# GPIO.net
KiCad netlist of a schematic drawn in Altium Designer
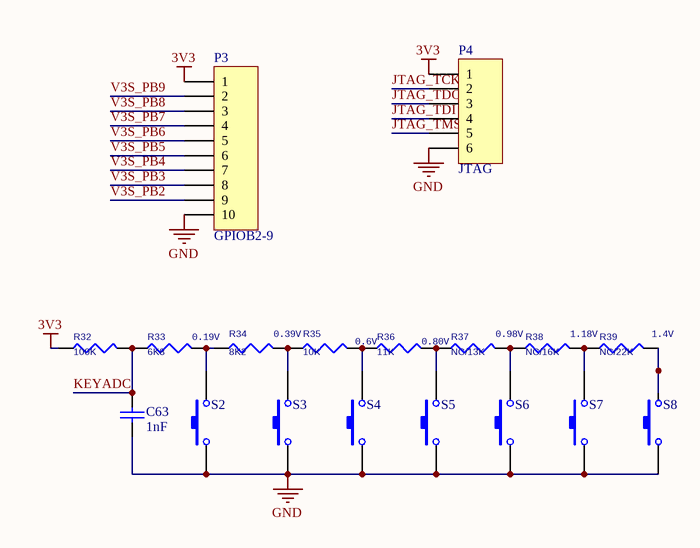
[diagram p0: GPIO.SchDoc]

(export (version "E")
  (design (tool "Eeschema 10.0.6"))
  (components
    (comp (ref "C63")
      (value "1nF")
      (footprint "0603C")
      (description "0603 Ceramic Capacitor")
      (fields (field (name "Comment") "103") (field (name "PUBLISHER") "Altium Limited"))
      (libsource (lib "Miscellaneous Devices") (part "Cap"))
    )
    (comp (ref "P3")
      (value "GPIOB2-9")
      (footprint "HDR1X10")
      (description "Header, 10-Pin")
      (fields (field (name "PUBLISHER") "Altium Limited"))
      (libsource (lib "Miscellaneous Connectors") (part "Header 10"))
    )
    (comp (ref "P4")
      (value "JTAG")
      (footprint "HDR1X6")
      (description "Header, 6-Pin")
      (fields (field (name "PUBLISHER") "Altium Limited"))
      (libsource (lib "Miscellaneous Connectors") (part "Header 6"))
    )
    (comp (ref "R32") (value "100K") (footprint "0603R") (libsource (lib "*") (part "R1 0805_Dup2")))
    (comp (ref "R33") (value "6K8") (footprint "0603R") (libsource (lib "*") (part "R1 0805_Dup2")))
    (comp (ref "R34") (value "8K2") (footprint "0603R") (libsource (lib "*") (part "R1 0805_Dup2")))
    (comp (ref "R35") (value "10K") (footprint "0603R") (libsource (lib "*") (part "R1 0805_Dup2")))
    (comp (ref "R36") (value "11K") (footprint "0603R") (libsource (lib "*") (part "R1 0805_Dup2")))
    (comp (ref "R37") (value "NC/13K") (footprint "0603R") (libsource (lib "*") (part "R1 0805")))
    (comp (ref "R38") (value "NC/16K") (footprint "0603R") (libsource (lib "*") (part "R1 0805")))
    (comp (ref "R39") (value "NC/22K") (footprint "0603R") (libsource (lib "*") (part "R1 0805")))
    (comp (ref "S2")
      (value "SW-PB")
      (footprint "Switch_SMT-022S-H2.5")
      (description "Switch")
      (fields (field (name "PUBLISHER") "Altium Limited"))
      (libsource (lib "Miscellaneous Devices") (part "SW-PB"))
    )
    (comp (ref "S3")
      (value "SW-PB")
      (footprint "Switch_SMT-022S-H2.5")
      (description "Switch")
      (fields (field (name "PUBLISHER") "Altium Limited"))
      (libsource (lib "Miscellaneous Devices") (part "SW-PB"))
    )
    (comp (ref "S4")
      (value "SW-PB")
      (footprint "Switch_SMT-022S-H2.5")
      (description "Switch")
      (fields (field (name "PUBLISHER") "Altium Limited"))
      (libsource (lib "Miscellaneous Devices") (part "SW-PB"))
    )
    (comp (ref "S5")
      (value "SW-PB")
      (footprint "Switch_SMT-022S-H2.5")
      (description "Switch")
      (fields (field (name "PUBLISHER") "Altium Limited"))
      (libsource (lib "Miscellaneous Devices") (part "SW-PB"))
    )
    (comp (ref "S6")
      (value "SW-PB")
      (footprint "Switch_SMT-022S-H2.5")
      (description "Switch")
      (fields (field (name "PUBLISHER") "Altium Limited"))
      (libsource (lib "Miscellaneous Devices") (part "SW-PB"))
    )
    (comp (ref "S7")
      (value "SW-PB")
      (footprint "Switch_SMT-022S-H2.5")
      (description "Switch")
      (fields (field (name "PUBLISHER") "Altium Limited"))
      (libsource (lib "Miscellaneous Devices") (part "SW-PB"))
    )
    (comp (ref "S8")
      (value "SW-PB")
      (footprint "Switch_SMT-022S-H2.5")
      (description "Switch")
      (fields (field (name "PUBLISHER") "Altium Limited"))
      (libsource (lib "Miscellaneous Devices") (part "SW-PB"))
    )
  )
  (nets
    (net (code "1") (name "/JTAG_TCK") (class "Default")
      (node (ref "P4") (pin "2") (pinfunction "2_2") (pintype "passive"))
    )
    (net (code "2") (name "/JTAG_TDI") (class "Default")
      (node (ref "P4") (pin "4") (pinfunction "4_4") (pintype "passive"))
    )
    (net (code "3") (name "/JTAG_TDO") (class "Default")
      (node (ref "P4") (pin "3") (pinfunction "3_3") (pintype "passive"))
    )
    (net (code "4") (name "/JTAG_TMS") (class "Default")
      (node (ref "P4") (pin "5") (pinfunction "5_5") (pintype "passive"))
    )
    (net (code "5") (name "/KEYADC") (class "Default")
      (node (ref "C63") (pin "1") (pinfunction "1_1") (pintype "passive"))
      (node (ref "R32") (pin "2") (pinfunction "2_2") (pintype "passive"))
      (node (ref "R33") (pin "1") (pinfunction "1_1") (pintype "passive"))
    )
    (net (code "6") (name "/V3S_PB2") (class "Default")
      (node (ref "P3") (pin "9") (pinfunction "9_9") (pintype "passive"))
    )
    (net (code "7") (name "/V3S_PB3") (class "Default")
      (node (ref "P3") (pin "8") (pinfunction "8_8") (pintype "passive"))
    )
    (net (code "8") (name "/V3S_PB4") (class "Default")
      (node (ref "P3") (pin "7") (pinfunction "7_7") (pintype "passive"))
    )
    (net (code "9") (name "/V3S_PB5") (class "Default")
      (node (ref "P3") (pin "6") (pinfunction "6_6") (pintype "passive"))
    )
    (net (code "10") (name "/V3S_PB6") (class "Default")
      (node (ref "P3") (pin "5") (pinfunction "5_5") (pintype "passive"))
    )
    (net (code "11") (name "/V3S_PB7") (class "Default")
      (node (ref "P3") (pin "4") (pinfunction "4_4") (pintype "passive"))
    )
    (net (code "12") (name "/V3S_PB8") (class "Default")
      (node (ref "P3") (pin "3") (pinfunction "3_3") (pintype "passive"))
    )
    (net (code "13") (name "/V3S_PB9") (class "Default")
      (node (ref "P3") (pin "2") (pinfunction "2_2") (pintype "passive"))
    )
    (net (code "14") (name "3V3") (class "Default")
      (node (ref "P3") (pin "1") (pinfunction "1_1") (pintype "passive"))
      (node (ref "P4") (pin "1") (pinfunction "1_1") (pintype "passive"))
      (node (ref "R32") (pin "1") (pinfunction "1_1") (pintype "passive"))
    )
    (net (code "15") (name "GND") (class "Default")
      (node (ref "C63") (pin "2") (pinfunction "2_2") (pintype "passive"))
      (node (ref "P3") (pin "10") (pinfunction "10_10") (pintype "passive"))
      (node (ref "P4") (pin "6") (pinfunction "6_6") (pintype "passive"))
      (node (ref "S2") (pin "1") (pinfunction "1_1") (pintype "passive"))
      (node (ref "S3") (pin "1") (pinfunction "1_1") (pintype "passive"))
      (node (ref "S4") (pin "1") (pinfunction "1_1") (pintype "passive"))
      (node (ref "S5") (pin "1") (pinfunction "1_1") (pintype "passive"))
      (node (ref "S6") (pin "1") (pinfunction "1_1") (pintype "passive"))
      (node (ref "S7") (pin "1") (pinfunction "1_1") (pintype "passive"))
      (node (ref "S8") (pin "1") (pinfunction "1_1") (pintype "passive"))
    )
    (net (code "16") (name "Net-(R33-Pad2)") (class "Default")
      (node (ref "R33") (pin "2") (pinfunction "2_2") (pintype "passive"))
      (node (ref "R34") (pin "1") (pinfunction "1_1") (pintype "passive"))
      (node (ref "S2") (pin "2") (pinfunction "2_2") (pintype "passive"))
    )
    (net (code "17") (name "Net-(R34-Pad2)") (class "Default")
      (node (ref "R34") (pin "2") (pinfunction "2_2") (pintype "passive"))
      (node (ref "R35") (pin "1") (pinfunction "1_1") (pintype "passive"))
      (node (ref "S3") (pin "2") (pinfunction "2_2") (pintype "passive"))
    )
    (net (code "18") (name "Net-(R35-Pad2)") (class "Default")
      (node (ref "R35") (pin "2") (pinfunction "2_2") (pintype "passive"))
      (node (ref "R36") (pin "1") (pinfunction "1_1") (pintype "passive"))
      (node (ref "S4") (pin "2") (pinfunction "2_2") (pintype "passive"))
    )
    (net (code "19") (name "Net-(R36-Pad2)") (class "Default")
      (node (ref "R36") (pin "2") (pinfunction "2_2") (pintype "passive"))
      (node (ref "R37") (pin "1") (pinfunction "1_1") (pintype "passive"))
      (node (ref "S5") (pin "2") (pinfunction "2_2") (pintype "passive"))
    )
    (net (code "20") (name "Net-(R37-Pad2)") (class "Default")
      (node (ref "R37") (pin "2") (pinfunction "2_2") (pintype "passive"))
      (node (ref "R38") (pin "1") (pinfunction "1_1") (pintype "passive"))
      (node (ref "S6") (pin "2") (pinfunction "2_2") (pintype "passive"))
    )
    (net (code "21") (name "Net-(R38-Pad2)") (class "Default")
      (node (ref "R38") (pin "2") (pinfunction "2_2") (pintype "passive"))
      (node (ref "R39") (pin "1") (pinfunction "1_1") (pintype "passive"))
      (node (ref "S7") (pin "2") (pinfunction "2_2") (pintype "passive"))
    )
    (net (code "22") (name "Net-(R39-Pad2)") (class "Default")
      (node (ref "R39") (pin "2") (pinfunction "2_2") (pintype "passive"))
      (node (ref "S8") (pin "2") (pinfunction "2_2") (pintype "passive"))
    )
  )
)
